# SH8_-_MICROCONTROLLER.net
KiCad netlist of a schematic drawn in Altium Designer
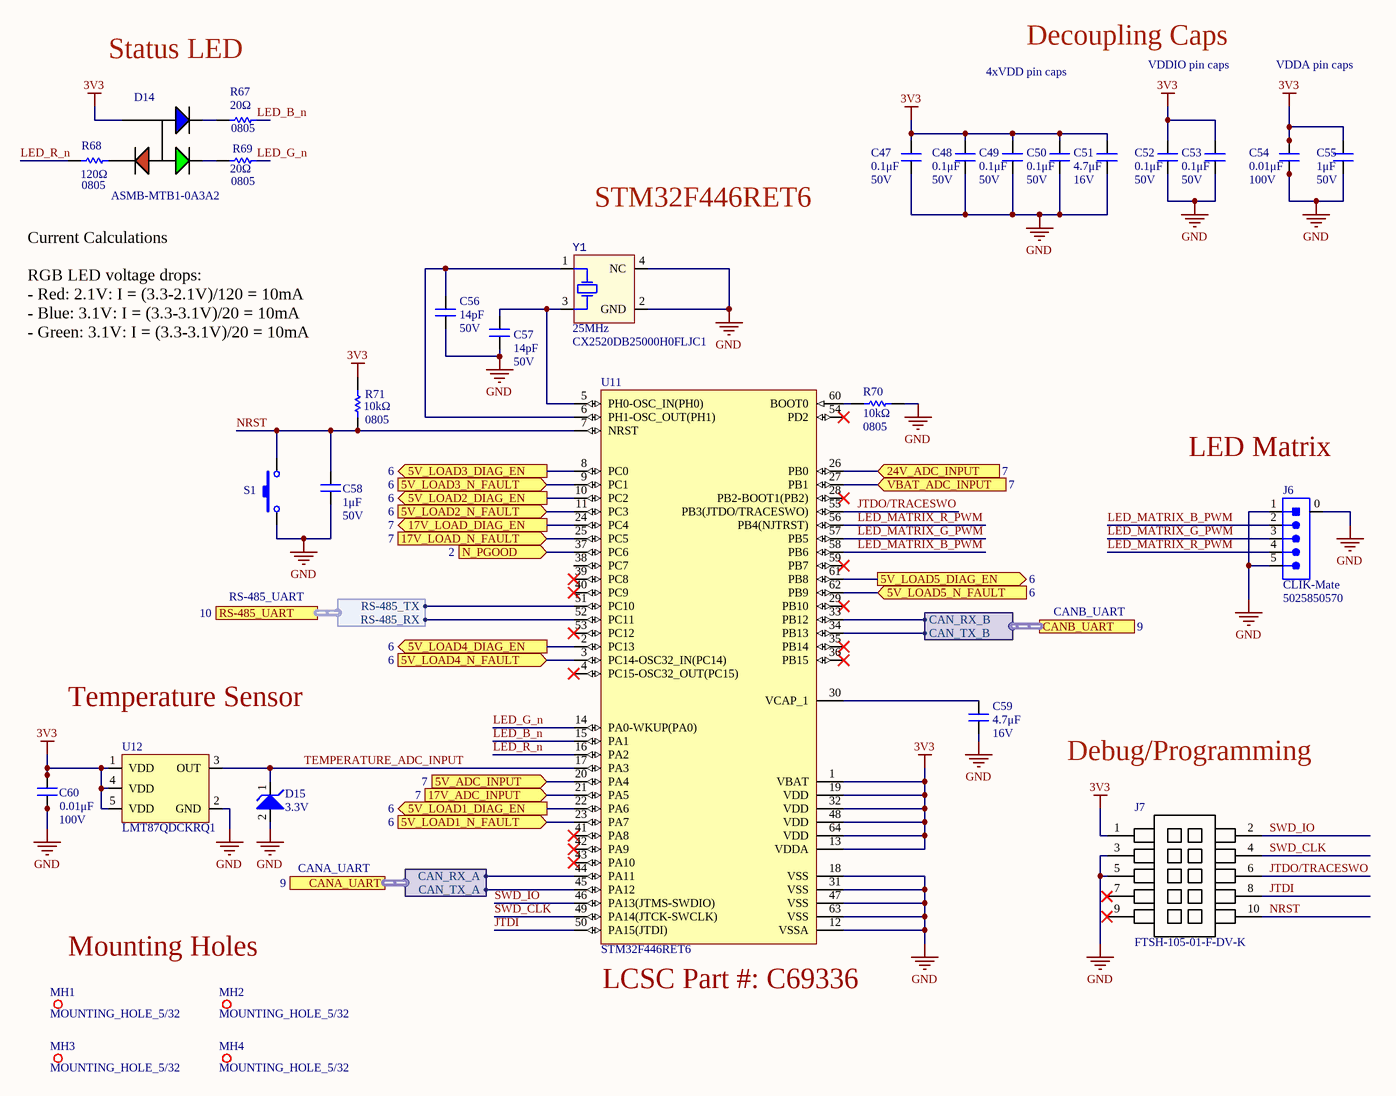
[diagram p0: SH8 - MICROCONTROLLER.SchDoc]

(export (version "E")
  (design (tool "Eeschema 10.0.6"))
  (components
    (comp (ref "C47")
      (value "0.1μF")
      (footprint "CAP2012")
      (description "CAP CER 0.1UF 50V X7R 0805")
      (fields
        (field (name "VOLTAGE RATING") "50V")
        (field (name "TOLERANCE") "10%")
        (field (name "LCSC PART #") "C49678")
      )
      (libsource (lib "UWRT_Schematic_Library_2020") (part "CAP_0.1uF_50V_0805"))
    )
    (comp (ref "C48")
      (value "0.1μF")
      (footprint "CAP2012")
      (description "CAP CER 0.1UF 50V X7R 0805")
      (fields
        (field (name "VOLTAGE RATING") "50V")
        (field (name "TOLERANCE") "10%")
        (field (name "LCSC PART #") "C49678")
      )
      (libsource (lib "UWRT_Schematic_Library_2020") (part "CAP_0.1uF_50V_0805"))
    )
    (comp (ref "C49")
      (value "0.1μF")
      (footprint "CAP2012")
      (description "CAP CER 0.1UF 50V X7R 0805")
      (fields
        (field (name "VOLTAGE RATING") "50V")
        (field (name "TOLERANCE") "10%")
        (field (name "LCSC PART #") "C49678")
      )
      (libsource (lib "UWRT_Schematic_Library_2020") (part "CAP_0.1uF_50V_0805"))
    )
    (comp (ref "C50")
      (value "0.1μF")
      (footprint "CAP2012")
      (description "CAP CER 0.1UF 50V X7R 0805")
      (fields
        (field (name "VOLTAGE RATING") "50V")
        (field (name "TOLERANCE") "10%")
        (field (name "LCSC PART #") "C49678")
      )
      (libsource (lib "UWRT_Schematic_Library_2020") (part "CAP_0.1uF_50V_0805"))
    )
    (comp (ref "C51")
      (value "4.7μF")
      (footprint "CAP2012")
      (description "CAP CER 4.7UF 16V X5R 0805")
      (fields
        (field (name "VOLTAGE RATING") "16V")
        (field (name "LCSC PART #") "C1779")
        (field (name "Comment") "CAP_4.7uF_16V_0805")
      )
      (libsource (lib "UWRT_Schematic_Library_2020") (part "CAP_4.7uF_16V_0805"))
    )
    (comp (ref "C52")
      (value "0.1μF")
      (footprint "CAP2012")
      (description "CAP CER 0.1UF 50V X7R 0805")
      (fields
        (field (name "VOLTAGE RATING") "50V")
        (field (name "TOLERANCE") "10%")
        (field (name "LCSC PART #") "C49678")
      )
      (libsource (lib "UWRT_Schematic_Library_2020") (part "CAP_0.1uF_50V_0805"))
    )
    (comp (ref "C53")
      (value "0.1μF")
      (footprint "CAP2012")
      (description "CAP CER 0.1UF 50V X7R 0805")
      (fields
        (field (name "VOLTAGE RATING") "50V")
        (field (name "TOLERANCE") "10%")
        (field (name "LCSC PART #") "C49678")
      )
      (libsource (lib "UWRT_Schematic_Library_2020") (part "CAP_0.1uF_50V_0805"))
    )
    (comp (ref "C54")
      (value "0.01μF")
      (footprint "CAP2012")
      (description "CAP CER 10000PF 100V X7R 0805")
      (fields
        (field (name "VOLTAGE RATING") "100V")
        (field (name "LCSC PART #") "C1710")
        (field (name "Comment") "CAP_0.01uF_100V_0805")
      )
      (libsource (lib "UWRT_Schematic_Library_2020") (part "CAP_0.01uF_100V_0805"))
    )
    (comp (ref "C55")
      (value "1μF")
      (footprint "CAP2012")
      (description "CAP CER 1UF 50V X7R 0805")
      (fields
        (field (name "VOLTAGE RATING") "50V")
        (field (name "LCSC PART #") "C28323")
        (field (name "Comment") "CAP_1uF_50V_0805")
      )
      (libsource (lib "UWRT_Schematic_Library_2020") (part "CAP_1uF_50V_0805"))
    )
    (comp (ref "C56")
      (value "14pF")
      (footprint "CAP0603")
      (description "CAP CER 14PF 50V C0G/NP0 0603")
      (fields (field (name "VOLTAGE RATING") "50V") (field (name "Comment") "CAP_14pF_50V_0603"))
      (libsource (lib "UWRT_Schematic_Library_2020") (part "CAP_14pF_50V_0603"))
    )
    (comp (ref "C57")
      (value "14pF")
      (footprint "CAP0603")
      (description "CAP CER 14PF 50V C0G/NP0 0603")
      (fields (field (name "VOLTAGE RATING") "50V") (field (name "Comment") "CAP_14pF_50V_0603"))
      (libsource (lib "UWRT_Schematic_Library_2020") (part "CAP_14pF_50V_0603"))
    )
    (comp (ref "C58")
      (value "1μF")
      (footprint "CAP2012")
      (description "CAP CER 1UF 50V X7R 0805")
      (fields
        (field (name "VOLTAGE RATING") "50V")
        (field (name "LCSC PART #") "C28323")
        (field (name "Comment") "CAP_1uF_50V_0805")
      )
      (libsource (lib "UWRT_Schematic_Library_2020") (part "CAP_1uF_50V_0805"))
    )
    (comp (ref "C59")
      (value "4.7μF")
      (footprint "CAP2012")
      (description "CAP CER 4.7UF 16V X5R 0805")
      (fields
        (field (name "VOLTAGE RATING") "16V")
        (field (name "LCSC PART #") "C1779")
        (field (name "Comment") "CAP_4.7uF_16V_0805")
      )
      (libsource (lib "UWRT_Schematic_Library_2020") (part "CAP_4.7uF_16V_0805"))
    )
    (comp (ref "C60")
      (value "0.01μF")
      (footprint "CAP2012")
      (description "CAP CER 10000PF 100V X7R 0805")
      (fields
        (field (name "VOLTAGE RATING") "100V")
        (field (name "LCSC PART #") "C1710")
        (field (name "Comment") "CAP_0.01uF_100V_0805")
      )
      (libsource (lib "UWRT_Schematic_Library_2020") (part "CAP_0.01uF_100V_0805"))
    )
    (comp (ref "D14")
      (value "LED_RGB")
      (footprint "LED_RGB")
      (description "LED RGB DIFFUSED 4PLCC SMD")
      (fields (field (name "MANUFACTURER PART NUMBER 1") "ASMB-MTB1-0A3A2"))
      (libsource (lib "UWRT_Schematic_Library_2020") (part "LED_RGB"))
    )
    (comp (ref "D15")
      (value "TVS_DIODE_UNIDIR_3.3V")
      (footprint "SOD523")
      (description "TVS DIODE 3.3V 14.1V SOD523")
      (fields (field (name "REVERSE STANDOFF VOLTAGE") "3.3V") (field (name "LCSC PART #") "C61148"))
      (libsource (lib "UWRT_Schematic_Library_2020") (part "TVS_DIODE_UNIDIR_3.3V"))
    )
    (comp (ref "J6")
      (value "CON_5M_SM_RA")
      (footprint "MOLEX-5025850570")
      (description "CONN HEADER SMD RIGHT ANGLE 1.5MM PITCH")
      (fields (field (name "FAMILY") "CLIK-Mate") (field (name "MANUFACTURER PART NUMBER 1") "5025850570"))
      (libsource (lib "UWRT_Schematic_Library_2020") (part "CON_5M_SM_RA"))
    )
    (comp (ref "J7")
      (value "CON_PROGRAMMING")
      (footprint "FTSH-105-01-F-DV-K-P-TR")
      (description "CONN HEADER SMD 10POS 1.27MM")
      (fields (field (name "MANUFACTURER PART NUMBER 1") "FTSH-105-01-F-DV-K"))
      (libsource (lib "UWRT_Schematic_Library_2020") (part "CON_PROGRAMMING"))
    )
    (comp (ref "MH1")
      (value "MOUNTING_HOLE_5/32")
      (footprint "MOUNTING_HOLE_5/38")
      (libsource (lib "UWRT_Schematic_Library_2020") (part "MOUNTING_HOLE_5/32"))
    )
    (comp (ref "MH2")
      (value "MOUNTING_HOLE_5/32")
      (footprint "MOUNTING_HOLE_5/38")
      (libsource (lib "UWRT_Schematic_Library_2020") (part "MOUNTING_HOLE_5/32"))
    )
    (comp (ref "MH3")
      (value "MOUNTING_HOLE_5/32")
      (footprint "MOUNTING_HOLE_5/38")
      (libsource (lib "UWRT_Schematic_Library_2020") (part "MOUNTING_HOLE_5/32"))
    )
    (comp (ref "MH4")
      (value "MOUNTING_HOLE_5/32")
      (footprint "MOUNTING_HOLE_5/38")
      (libsource (lib "UWRT_Schematic_Library_2020") (part "MOUNTING_HOLE_5/32"))
    )
    (comp (ref "R67")
      (value "20Ω")
      (footprint "RESC0805")
      (description "RES 20 OHM 1% 1/8W 0805")
      (fields
        (field (name "TOLERANCE") "1%")
        (field (name "LCSC PART #") "C17581")
        (field (name "PACKAGE/FOOTPRINT") "0805")
      )
      (libsource (lib "UWRT_Schematic_Library_2020") (part "RES_20Ω_0805_1%"))
    )
    (comp (ref "R68")
      (value "RES_120Ω_0805_1%")
      (footprint "RESC0805")
      (description "RES 120 OHM 1% 1/8W 0805")
      (fields
        (field (name "RESISTANCE") "120Ω")
        (field (name "LCSC PART #") "C17437")
        (field (name "PACKAGE/FOOTPRINT") "0805")
      )
      (libsource (lib "UWRT_Schematic_Library_2020") (part "RES_120Ω_0805_1%"))
    )
    (comp (ref "R69")
      (value "20Ω")
      (footprint "RESC0805")
      (description "RES 20 OHM 1% 1/8W 0805")
      (fields
        (field (name "TOLERANCE") "1%")
        (field (name "LCSC PART #") "C17581")
        (field (name "PACKAGE/FOOTPRINT") "0805")
      )
      (libsource (lib "UWRT_Schematic_Library_2020") (part "RES_20Ω_0805_1%"))
    )
    (comp (ref "R70")
      (value "10kΩ")
      (footprint "RESC0805")
      (description "RES 10K OHM 5% 1/8W 0805")
      (fields
        (field (name "LCSC PART #") "C17414")
        (field (name "PACKAGE/FOOTPRINT") "0805")
        (field (name "Comment") "RES_10kΩ_0805_5%")
      )
      (libsource (lib "UWRT_Schematic_Library_2020") (part "RES_10kΩ_0805_5%"))
    )
    (comp (ref "R71")
      (value "10kΩ")
      (footprint "RESC0805")
      (description "RES 10K OHM 5% 1/8W 0805")
      (fields
        (field (name "LCSC PART #") "C17414")
        (field (name "PACKAGE/FOOTPRINT") "0805")
        (field (name "Comment") "RES_10kΩ_0805_5%")
      )
      (libsource (lib "UWRT_Schematic_Library_2020") (part "RES_10kΩ_0805_5%"))
    )
    (comp (ref "S1")
      (value "SW_TACTILE")
      (footprint "B3U-1000P")
      (description "SWITCH TACTILE SPST-NO 0.05A 12V")
      (libsource (lib "UWRT_Schematic_Library_2020") (part "SW_TACTILE"))
    )
    (comp (ref "U11")
      (value "STM32F446RET6")
      (footprint "STM-LQFP64_L")
      (libsource (lib "UWRT_Schematic_Library_2020") (part "MCU_STM32F446RET6"))
    )
    (comp (ref "U12")
      (value "IC TEMPERATURE_SENSOR")
      (footprint "SOT65P210X110-5N")
      (description "SENSOR ANALOG -50C-150C SC70")
      (fields
        (field (name "MANUFACTURER PART NUMBER 1") "LMT87QDCKRQ1")
        (field (name "LCSC PART #") "C206058")
      )
      (libsource (lib "UWRT_Schematic_Library_2020") (part "IC TEMPERATURE_SENSOR"))
    )
    (comp (ref "Y1")
      (value "CRYSTAL_25MHZ")
      (footprint "SOIC254P1016X440-4N")
      (description "CRYSTAL 25.0000MHZ 12PF SMD")
      (fields
        (field (name "FREQUENCY") "25MHz")
        (field (name "MANUFACTURER PART NUMBER 1") "CX2520DB25000H0FLJC1")
      )
      (libsource (lib "UWRT_Schematic_Library_2020") (part "CRYSTAL_25MHZ"))
    )
  )
  (nets
    (net (code "4") (name "/5V_ADC_INPUT") (class "Default")
      (node (ref "U11") (pin "20") (pinfunction "PA4_20") (pintype "bidirectional"))
    )
    (net (code "5") (name "/5V_LOAD1_DIAG_EN") (class "Default")
      (node (ref "U11") (pin "22") (pinfunction "PA6_22") (pintype "bidirectional"))
    )
    (net (code "6") (name "/5V_LOAD1_N_FAULT") (class "Default")
      (node (ref "U11") (pin "23") (pinfunction "PA7_23") (pintype "bidirectional"))
    )
    (net (code "7") (name "/5V_LOAD2_DIAG_EN") (class "Default")
      (node (ref "U11") (pin "10") (pinfunction "PC2_10") (pintype "bidirectional"))
    )
    (net (code "8") (name "/5V_LOAD2_N_FAULT") (class "Default")
      (node (ref "U11") (pin "11") (pinfunction "PC3_11") (pintype "bidirectional"))
    )
    (net (code "9") (name "/5V_LOAD3_DIAG_EN") (class "Default")
      (node (ref "U11") (pin "8") (pinfunction "PC0_8") (pintype "bidirectional"))
    )
    (net (code "10") (name "/5V_LOAD3_N_FAULT") (class "Default")
      (node (ref "U11") (pin "9") (pinfunction "PC1_9") (pintype "bidirectional"))
    )
    (net (code "11") (name "/5V_LOAD4_DIAG_EN") (class "Default")
      (node (ref "U11") (pin "2") (pinfunction "PC13_2") (pintype "bidirectional"))
    )
    (net (code "12") (name "/5V_LOAD4_N_FAULT") (class "Default")
      (node (ref "U11") (pin "3") (pinfunction "PC14-OSC32_IN(PC14)_3") (pintype "bidirectional"))
    )
    (net (code "13") (name "/5V_LOAD5_DIAG_EN") (class "Default")
      (node (ref "U11") (pin "61") (pinfunction "PB8_61") (pintype "bidirectional"))
    )
    (net (code "14") (name "/5V_LOAD5_N_FAULT") (class "Default")
      (node (ref "U11") (pin "62") (pinfunction "PB9_62") (pintype "bidirectional"))
    )
    (net (code "15") (name "/17V_ADC_INPUT") (class "Default")
      (node (ref "U11") (pin "21") (pinfunction "PA5_21") (pintype "bidirectional"))
    )
    (net (code "16") (name "/17V_LOAD_DIAG_EN") (class "Default")
      (node (ref "U11") (pin "24") (pinfunction "PC4_24") (pintype "bidirectional"))
    )
    (net (code "17") (name "/17V_LOAD_N_FAULT") (class "Default")
      (node (ref "U11") (pin "25") (pinfunction "PC5_25") (pintype "bidirectional"))
    )
    (net (code "18") (name "/24V_ADC_INPUT") (class "Default")
      (node (ref "U11") (pin "26") (pinfunction "PB0_26") (pintype "bidirectional"))
    )
    (net (code "19") (name "/CAN_RX_A") (class "Default")
      (node (ref "U11") (pin "44") (pinfunction "PA11_44") (pintype "bidirectional"))
    )
    (net (code "20") (name "/CAN_RX_B") (class "Default")
      (node (ref "U11") (pin "33") (pinfunction "PB12_33") (pintype "bidirectional"))
    )
    (net (code "21") (name "/CAN_TX_A") (class "Default")
      (node (ref "U11") (pin "45") (pinfunction "PA12_45") (pintype "bidirectional"))
    )
    (net (code "22") (name "/CAN_TX_B") (class "Default")
      (node (ref "U11") (pin "34") (pinfunction "PB13_34") (pintype "bidirectional"))
    )
    (net (code "23") (name "/JTDI") (class "Default")
      (node (ref "J7") (pin "8") (pinfunction "8_8") (pintype "passive"))
      (node (ref "U11") (pin "50") (pinfunction "PA15(JTDI)_50") (pintype "bidirectional"))
    )
    (net (code "24") (name "/JTDO{slash}TRACESWO") (class "Default")
      (node (ref "J7") (pin "6") (pinfunction "6_6") (pintype "passive"))
      (node (ref "U11") (pin "55") (pinfunction "PB3(JTDO/TRACESWO)_55") (pintype "bidirectional"))
    )
    (net (code "25") (name "/LED_B_n") (class "Default")
      (node (ref "R67") (pin "2") (pinfunction "2_2") (pintype "passive"))
      (node (ref "U11") (pin "15") (pinfunction "PA1_15") (pintype "bidirectional"))
    )
    (net (code "26") (name "/LED_G_n") (class "Default")
      (node (ref "R69") (pin "2") (pinfunction "2_2") (pintype "passive"))
      (node (ref "U11") (pin "14") (pinfunction "PA0-WKUP(PA0)_14") (pintype "bidirectional"))
    )
    (net (code "27") (name "/LED_MATRIX_B_PWM") (class "Default")
      (node (ref "J6") (pin "2") (pinfunction "2_2") (pintype "passive"))
      (node (ref "U11") (pin "58") (pinfunction "PB6_58") (pintype "bidirectional"))
    )
    (net (code "28") (name "/LED_MATRIX_G_PWM") (class "Default")
      (node (ref "J6") (pin "3") (pinfunction "3_3") (pintype "passive"))
      (node (ref "U11") (pin "57") (pinfunction "PB5_57") (pintype "bidirectional"))
    )
    (net (code "29") (name "/LED_MATRIX_R_PWM") (class "Default")
      (node (ref "J6") (pin "4") (pinfunction "4_4") (pintype "passive"))
      (node (ref "U11") (pin "56") (pinfunction "PB4(NJTRST)_56") (pintype "bidirectional"))
    )
    (net (code "30") (name "/LED_R_n") (class "Default")
      (node (ref "R68") (pin "1") (pinfunction "1_1") (pintype "passive"))
      (node (ref "U11") (pin "16") (pinfunction "PA2_16") (pintype "bidirectional"))
    )
    (net (code "31") (name "/NRST") (class "Default")
      (node (ref "C58") (pin "2") (pinfunction "2_2") (pintype "passive"))
      (node (ref "J7") (pin "10") (pinfunction "10_10") (pintype "passive"))
      (node (ref "R71") (pin "1") (pinfunction "1_1") (pintype "passive"))
      (node (ref "S1") (pin "2") (pinfunction "2_2") (pintype "passive"))
      (node (ref "U11") (pin "7") (pinfunction "NRST_7") (pintype "bidirectional"))
    )
    (net (code "32") (name "/N_PGOOD") (class "Default")
      (node (ref "U11") (pin "37") (pinfunction "PC6_37") (pintype "bidirectional"))
    )
    (net (code "33") (name "/RS-485_RX") (class "Default")
      (node (ref "U11") (pin "52") (pinfunction "PC11_52") (pintype "bidirectional"))
    )
    (net (code "34") (name "/RS-485_TX") (class "Default")
      (node (ref "U11") (pin "51") (pinfunction "PC10_51") (pintype "bidirectional"))
    )
    (net (code "35") (name "/SWD_CLK") (class "Default")
      (node (ref "J7") (pin "4") (pinfunction "4_4") (pintype "passive"))
      (node (ref "U11") (pin "49") (pinfunction "PA14(JTCK-SWCLK)_49") (pintype "bidirectional"))
    )
    (net (code "36") (name "/SWD_IO") (class "Default")
      (node (ref "J7") (pin "2") (pinfunction "2_2") (pintype "passive"))
      (node (ref "U11") (pin "46") (pinfunction "PA13(JTMS-SWDIO)_46") (pintype "bidirectional"))
    )
    (net (code "37") (name "/TEMPERATURE_ADC_INPUT") (class "Default")
      (node (ref "D15") (pin "1") (pinfunction "1_1") (pintype "passive"))
      (node (ref "U11") (pin "17") (pinfunction "PA3_17") (pintype "bidirectional"))
      (node (ref "U12") (pin "3") (pinfunction "OUT_3") (pintype "passive"))
    )
    (net (code "38") (name "/VBAT_ADC_INPUT") (class "Default")
      (node (ref "U11") (pin "27") (pinfunction "PB1_27") (pintype "bidirectional"))
    )
    (net (code "42") (name "3V3") (class "Default")
      (node (ref "C47") (pin "2") (pinfunction "2_2") (pintype "passive"))
      (node (ref "C48") (pin "2") (pinfunction "2_2") (pintype "passive"))
      (node (ref "C49") (pin "2") (pinfunction "2_2") (pintype "passive"))
      (node (ref "C50") (pin "2") (pinfunction "2_2") (pintype "passive"))
      (node (ref "C51") (pin "2") (pinfunction "2_2") (pintype "passive"))
      (node (ref "C52") (pin "2") (pinfunction "2_2") (pintype "passive"))
      (node (ref "C53") (pin "2") (pinfunction "2_2") (pintype "passive"))
      (node (ref "C54") (pin "2") (pinfunction "2_2") (pintype "passive"))
      (node (ref "C55") (pin "2") (pinfunction "2_2") (pintype "passive"))
      (node (ref "C60") (pin "2") (pinfunction "2_2") (pintype "passive"))
      (node (ref "D14") (pin "4") (pinfunction "COMMON_ANODE_4") (pintype "passive"))
      (node (ref "J7") (pin "1") (pinfunction "1_1") (pintype "passive"))
      (node (ref "R71") (pin "2") (pinfunction "2_2") (pintype "passive"))
      (node (ref "U11") (pin "1") (pinfunction "VBAT_1") (pintype "power_in"))
      (node (ref "U11") (pin "13") (pinfunction "VDDA_13") (pintype "power_in"))
      (node (ref "U11") (pin "19") (pinfunction "VDD_19") (pintype "power_in"))
      (node (ref "U11") (pin "32") (pinfunction "VDD_32") (pintype "power_in"))
      (node (ref "U11") (pin "48") (pinfunction "VDD_48") (pintype "power_in"))
      (node (ref "U11") (pin "64") (pinfunction "VDD_64") (pintype "power_in"))
      (node (ref "U12") (pin "1") (pinfunction "VDD_1") (pintype "passive"))
      (node (ref "U12") (pin "4") (pinfunction "VDD_4") (pintype "passive"))
      (node (ref "U12") (pin "5") (pinfunction "VDD_5") (pintype "passive"))
    )
    (net (code "43") (name "GND") (class "Default")
      (node (ref "C47") (pin "1") (pinfunction "1_1") (pintype "passive"))
      (node (ref "C48") (pin "1") (pinfunction "1_1") (pintype "passive"))
      (node (ref "C49") (pin "1") (pinfunction "1_1") (pintype "passive"))
      (node (ref "C50") (pin "1") (pinfunction "1_1") (pintype "passive"))
      (node (ref "C51") (pin "1") (pinfunction "1_1") (pintype "passive"))
      (node (ref "C52") (pin "1") (pinfunction "1_1") (pintype "passive"))
      (node (ref "C53") (pin "1") (pinfunction "1_1") (pintype "passive"))
      (node (ref "C54") (pin "1") (pinfunction "1_1") (pintype "passive"))
      (node (ref "C55") (pin "1") (pinfunction "1_1") (pintype "passive"))
      (node (ref "C56") (pin "1") (pinfunction "1_1") (pintype "passive"))
      (node (ref "C57") (pin "1") (pinfunction "1_1") (pintype "passive"))
      (node (ref "C58") (pin "1") (pinfunction "1_1") (pintype "passive"))
      (node (ref "C59") (pin "1") (pinfunction "1_1") (pintype "passive"))
      (node (ref "C60") (pin "1") (pinfunction "1_1") (pintype "passive"))
      (node (ref "D15") (pin "2") (pinfunction "2_2") (pintype "passive"))
      (node (ref "J6") (pin "0") (pinfunction "0_0") (pintype "passive"))
      (node (ref "J6") (pin "1") (pinfunction "1_1") (pintype "passive"))
      (node (ref "J6") (pin "5") (pinfunction "5_5") (pintype "passive"))
      (node (ref "J7") (pin "3") (pinfunction "3_3") (pintype "passive"))
      (node (ref "J7") (pin "5") (pinfunction "5_5") (pintype "passive"))
      (node (ref "R70") (pin "2") (pinfunction "2_2") (pintype "passive"))
      (node (ref "S1") (pin "1") (pinfunction "1_1") (pintype "passive"))
      (node (ref "U11") (pin "12") (pinfunction "VSSA_12") (pintype "power_in"))
      (node (ref "U11") (pin "18") (pinfunction "VSS_18") (pintype "power_in"))
      (node (ref "U11") (pin "31") (pinfunction "VSS_31") (pintype "power_in"))
      (node (ref "U11") (pin "47") (pinfunction "VSS_47") (pintype "power_in"))
      (node (ref "U11") (pin "63") (pinfunction "VSS_63") (pintype "power_in"))
      (node (ref "U12") (pin "2") (pinfunction "GND_2") (pintype "passive"))
      (node (ref "Y1") (pin "2") (pinfunction "GND_2") (pintype "power_in"))
      (node (ref "Y1") (pin "4") (pinfunction "NC_4") (pintype "passive"))
    )
    (net (code "44") (name "Net-(D14-CATHODE_(BLUE))") (class "Default")
      (node (ref "D14") (pin "3") (pinfunction "CATHODE_(BLUE)_3") (pintype "passive"))
      (node (ref "R67") (pin "1") (pinfunction "1_1") (pintype "passive"))
    )
    (net (code "45") (name "Net-(D14-CATHODE_(GREEN))") (class "Default")
      (node (ref "D14") (pin "2") (pinfunction "CATHODE_(GREEN)_2") (pintype "passive"))
      (node (ref "R69") (pin "1") (pinfunction "1_1") (pintype "passive"))
    )
    (net (code "46") (name "Net-(D14-CATHODE_(RED))") (class "Default")
      (node (ref "D14") (pin "1") (pinfunction "CATHODE_(RED)_1") (pintype "passive"))
      (node (ref "R68") (pin "2") (pinfunction "2_2") (pintype "passive"))
    )
    (net (code "47") (name "Net-(U11-BOOT0)") (class "Default")
      (node (ref "R70") (pin "1") (pinfunction "1_1") (pintype "passive"))
      (node (ref "U11") (pin "60") (pinfunction "BOOT0_60") (pintype "input"))
    )
    (net (code "48") (name "Net-(U11-PH0-OSC_IN(PH0))") (class "Default")
      (node (ref "C57") (pin "2") (pinfunction "2_2") (pintype "passive"))
      (node (ref "U11") (pin "5") (pinfunction "PH0-OSC_IN(PH0)_5") (pintype "bidirectional"))
      (node (ref "Y1") (pin "3") (pinfunction "HOT_3") (pintype "passive"))
    )
    (net (code "49") (name "Net-(U11-PH1-OSC_OUT(PH1))") (class "Default")
      (node (ref "C56") (pin "2") (pinfunction "2_2") (pintype "passive"))
      (node (ref "U11") (pin "6") (pinfunction "PH1-OSC_OUT(PH1)_6") (pintype "bidirectional"))
      (node (ref "Y1") (pin "1") (pinfunction "HOT_1") (pintype "passive"))
    )
    (net (code "50") (name "Net-(U11-VCAP_1)") (class "Default")
      (node (ref "C59") (pin "2") (pinfunction "2_2") (pintype "passive"))
      (node (ref "U11") (pin "30") (pinfunction "VCAP_1_30") (pintype "passive"))
    )
    (net (code "51") (name "unconnected-(J7-Pad7)") (class "Default")
      (node (ref "J7") (pin "7") (pinfunction "7_7") (pintype "passive+no_connect"))
    )
    (net (code "52") (name "unconnected-(J7-Pad9)") (class "Default")
      (node (ref "J7") (pin "9") (pinfunction "9_9") (pintype "passive+no_connect"))
    )
    (net (code "53") (name "unconnected-(U11-PA8-Pad41)") (class "Default")
      (node (ref "U11") (pin "41") (pinfunction "PA8_41") (pintype "bidirectional+no_connect"))
    )
    (net (code "54") (name "unconnected-(U11-PA9-Pad42)") (class "Default")
      (node (ref "U11") (pin "42") (pinfunction "PA9_42") (pintype "bidirectional+no_connect"))
    )
    (net (code "55") (name "unconnected-(U11-PA10-Pad43)") (class "Default")
      (node (ref "U11") (pin "43") (pinfunction "PA10_43") (pintype "bidirectional+no_connect"))
    )
    (net (code "56") (name "unconnected-(U11-PB2-BOOT1(PB2)-Pad28)") (class "Default")
      (node (ref "U11") (pin "28") (pinfunction "PB2-BOOT1(PB2)_28") (pintype "bidirectional+no_connect"))
    )
    (net (code "57") (name "unconnected-(U11-PB7-Pad59)") (class "Default")
      (node (ref "U11") (pin "59") (pinfunction "PB7_59") (pintype "bidirectional+no_connect"))
    )
    (net (code "58") (name "unconnected-(U11-PB10-Pad29)") (class "Default")
      (node (ref "U11") (pin "29") (pinfunction "PB10_29") (pintype "bidirectional+no_connect"))
    )
    (net (code "59") (name "unconnected-(U11-PB14-Pad35)") (class "Default")
      (node (ref "U11") (pin "35") (pinfunction "PB14_35") (pintype "bidirectional+no_connect"))
    )
    (net (code "60") (name "unconnected-(U11-PB15-Pad36)") (class "Default")
      (node (ref "U11") (pin "36") (pinfunction "PB15_36") (pintype "bidirectional+no_connect"))
    )
    (net (code "61") (name "unconnected-(U11-PC7-Pad38)") (class "Default")
      (node (ref "U11") (pin "38") (pinfunction "PC7_38") (pintype "bidirectional"))
    )
    (net (code "62") (name "unconnected-(U11-PC8-Pad39)") (class "Default")
      (node (ref "U11") (pin "39") (pinfunction "PC8_39") (pintype "bidirectional+no_connect"))
    )
    (net (code "63") (name "unconnected-(U11-PC9-Pad40)") (class "Default")
      (node (ref "U11") (pin "40") (pinfunction "PC9_40") (pintype "bidirectional+no_connect"))
    )
    (net (code "64") (name "unconnected-(U11-PC12-Pad53)") (class "Default")
      (node (ref "U11") (pin "53") (pinfunction "PC12_53") (pintype "bidirectional+no_connect"))
    )
    (net (code "65") (name "unconnected-(U11-PC15-OSC32_OUT(PC15)-Pad4)") (class "Default")
      (node (ref "U11") (pin "4") (pinfunction "PC15-OSC32_OUT(PC15)_4") (pintype "bidirectional+no_connect"))
    )
    (net (code "66") (name "unconnected-(U11-PD2-Pad54)") (class "Default")
      (node (ref "U11") (pin "54") (pinfunction "PD2_54") (pintype "bidirectional+no_connect"))
    )
  )
)
